# Bluetooth.net
KiCad netlist of a schematic drawn in Altium Designer
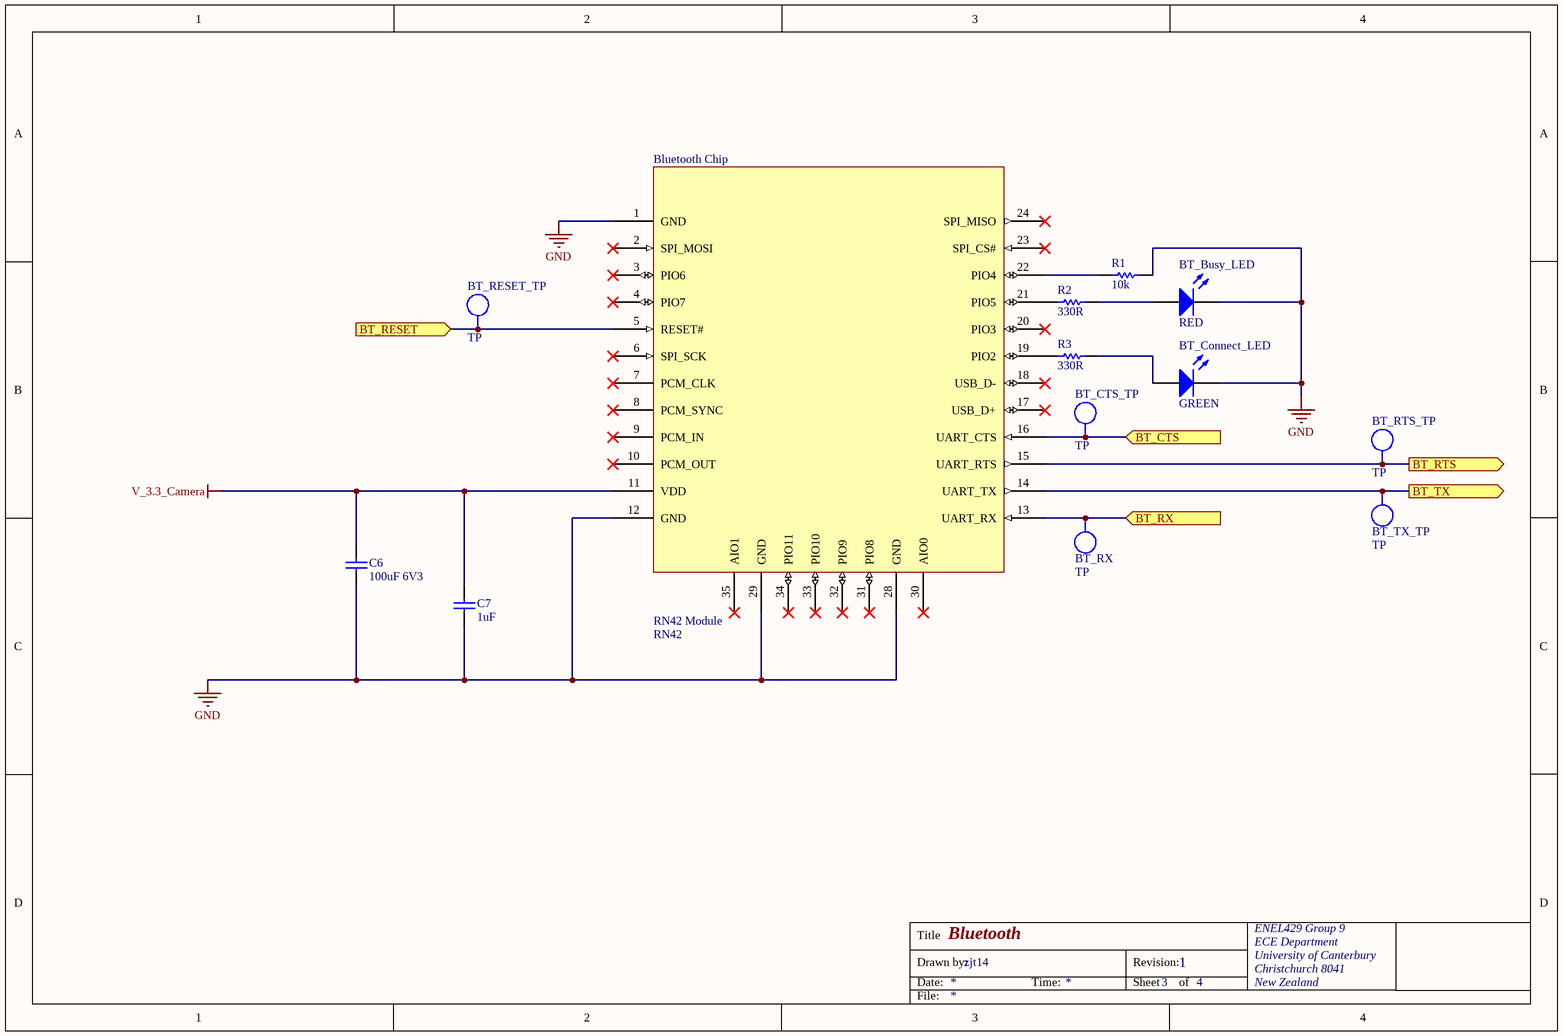
[diagram p0: Bluetooth.SchDoc]

(export (version "E")
  (design (tool "Eeschema 10.0.6"))
  (components
    (comp (ref "Bluetooth Chip")
      (value "RN42 Module")
      (footprint "RN42-LAND")
      (fields (field (name "ALTIUM_VALUE") "RN42") (field (name "MANUFACTURER") "Roving Networks"))
      (libsource (lib "Dwl-Altium-Schematic-Symbol-Library") (part "RN42MOD"))
    )
    (comp (ref "BT_Busy_LED")
      (value "RED")
      (footprint "Diode_0805")
      (description "Red LED 0805")
      (fields (field (name "PART NUMBER") "DL_LED Red 0805") (field (name "MANUFACTURER") "Vishay"))
      (libsource (lib "ENEL429_4") (part "DL_LED Red 0805"))
    )
    (comp (ref "BT_Connect_LED")
      (value "GREEN")
      (footprint "DIODE_0805")
      (description "Green LED 0805")
      (fields (field (name "PART NUMBER") "DL_LED Green 0805") (field (name "MANUFACTURER") "Vishay"))
      (libsource (lib "ENEL429_4") (part "DL_LED Green 0805"))
    )
    (comp (ref "BT_CTS_TP")
      (value "TP")
      (footprint "TEST_POINT_4X2MM")
      (description "Test-Point")
      (fields (field (name "PART NUMBER") "TP_TESTPOINT"))
      (libsource (lib "ENEL429_4") (part "TP_TESTPOINT"))
    )
    (comp (ref "BT_RESET_TP")
      (value "TP")
      (footprint "TEST_POINT_4X2MM")
      (description "Test-Point")
      (fields (field (name "PART NUMBER") "TP_TESTPOINT"))
      (libsource (lib "ENEL429_4") (part "TP_TESTPOINT"))
    )
    (comp (ref "BT_RTS_TP")
      (value "TP")
      (footprint "TEST_POINT_4X2MM")
      (description "Test-Point")
      (fields (field (name "PART NUMBER") "TP_TESTPOINT"))
      (libsource (lib "ENEL429_4") (part "TP_TESTPOINT"))
    )
    (comp (ref "BT_RX")
      (value "TP")
      (footprint "TEST_POINT_4X2MM")
      (description "Test-Point")
      (fields (field (name "PART NUMBER") "TP_TESTPOINT"))
      (libsource (lib "ENEL429_4") (part "TP_TESTPOINT"))
    )
    (comp (ref "BT_TX_TP")
      (value "TP")
      (footprint "TEST_POINT_4X2MM")
      (description "Test-Point")
      (fields (field (name "PART NUMBER") "TP_TESTPOINT"))
      (libsource (lib "ENEL429_4") (part "TP_TESTPOINT"))
    )
    (comp (ref "C6")
      (value "100uF 6V3")
      (footprint "1206")
      (description "100uF 6.3V 1206 multi-layer ceramic capacitor")
      (fields (field (name "PART NUMBER") "CP_CER 100uF_1206_6V3") (field (name "MANUFACTURER") "Kemet"))
      (libsource (lib "ENEL429_4") (part "CP_CER 100uF_1206_6V3"))
    )
    (comp (ref "C7")
      (value "1uF")
      (footprint "0603")
      (description "CAP CER 1.0UF 50V X7R 0603")
      (fields (field (name "PART NUMBER") "CP_1uF_50V_0603") (field (name "MANUFACTURER") "Taiyo Yuden"))
      (libsource (lib "ENEL429_4") (part "CP_1uF_50V_0603"))
    )
    (comp (ref "R1")
      (value "10k")
      (footprint "0603")
      (description "RES 10.0K OHM 1/10W 1% 0603 SMD")
      (fields (field (name "PART NUMBER") "RS_10k 0603") (field (name "MANUFACTURER") "Yageo"))
      (libsource (lib "ENEL429_4") (part "RS_10k 0603"))
    )
    (comp (ref "R2")
      (value "330R")
      (footprint "0603")
      (description "RES 330 OHM 1/10W 1% 0603 SMD")
      (fields (field (name "PART NUMBER") "RS_330R 0603") (field (name "MANUFACTURER") "Yageo"))
      (libsource (lib "ENEL429_4") (part "RS_330R 0603"))
    )
    (comp (ref "R3")
      (value "330R")
      (footprint "0603")
      (description "RES 330 OHM 1/10W 1% 0603 SMD")
      (fields (field (name "PART NUMBER") "RS_330R 0603") (field (name "MANUFACTURER") "Yageo"))
      (libsource (lib "ENEL429_4") (part "RS_330R 0603"))
    )
  )
  (nets
    (net (code "1") (name "/BT_CTS") (class "Default")
      (node (ref "BT_CTS_TP") (pin "1") (pinfunction "1_1") (pintype "passive"))
      (node (ref "Bluetooth Chip") (pin "16") (pinfunction "UART_CTS_16") (pintype "input"))
    )
    (net (code "2") (name "/BT_RESET") (class "Default")
      (node (ref "BT_RESET_TP") (pin "1") (pinfunction "1_1") (pintype "passive"))
      (node (ref "Bluetooth Chip") (pin "5") (pinfunction "RESET#_5") (pintype "input"))
    )
    (net (code "3") (name "/BT_RTS") (class "Default")
      (node (ref "BT_RTS_TP") (pin "1") (pinfunction "1_1") (pintype "passive"))
      (node (ref "Bluetooth Chip") (pin "15") (pinfunction "UART_RTS_15") (pintype "output"))
    )
    (net (code "4") (name "/BT_RX") (class "Default")
      (node (ref "BT_RX") (pin "1") (pinfunction "1_1") (pintype "passive"))
      (node (ref "Bluetooth Chip") (pin "13") (pinfunction "UART_RX_13") (pintype "input"))
    )
    (net (code "5") (name "/BT_TX") (class "Default")
      (node (ref "BT_TX_TP") (pin "1") (pinfunction "1_1") (pintype "passive"))
      (node (ref "Bluetooth Chip") (pin "14") (pinfunction "UART_TX_14") (pintype "output"))
    )
    (net (code "6") (name "GND") (class "Default")
      (node (ref "BT_Busy_LED") (pin "2") (pinfunction "K_2") (pintype "passive"))
      (node (ref "BT_Connect_LED") (pin "2") (pinfunction "K_2") (pintype "passive"))
      (node (ref "Bluetooth Chip") (pin "1") (pinfunction "GND_1") (pintype "power_in"))
      (node (ref "Bluetooth Chip") (pin "12") (pinfunction "GND_12") (pintype "power_in"))
      (node (ref "Bluetooth Chip") (pin "28") (pinfunction "GND_28") (pintype "power_in"))
      (node (ref "Bluetooth Chip") (pin "29") (pinfunction "GND_29") (pintype "power_in"))
      (node (ref "C6") (pin "2") (pinfunction "2_2") (pintype "passive"))
      (node (ref "C7") (pin "2") (pinfunction "2_2") (pintype "passive"))
      (node (ref "R1") (pin "2") (pinfunction "2_2") (pintype "passive"))
    )
    (net (code "7") (name "Net-(BT_Busy_LED-A)") (class "Default")
      (node (ref "BT_Busy_LED") (pin "1") (pinfunction "A_1") (pintype "passive"))
      (node (ref "R2") (pin "2") (pinfunction "2_2") (pintype "passive"))
    )
    (net (code "8") (name "Net-(BT_Connect_LED-A)") (class "Default")
      (node (ref "BT_Connect_LED") (pin "1") (pinfunction "A_1") (pintype "passive"))
      (node (ref "R3") (pin "2") (pinfunction "2_2") (pintype "passive"))
    )
    (net (code "9") (name "Net-(Bluetooth Chip-PIO2)") (class "Default")
      (node (ref "Bluetooth Chip") (pin "19") (pinfunction "PIO2_19") (pintype "bidirectional"))
      (node (ref "R3") (pin "1") (pinfunction "1_1") (pintype "passive"))
    )
    (net (code "10") (name "Net-(Bluetooth Chip-PIO4)") (class "Default")
      (node (ref "Bluetooth Chip") (pin "22") (pinfunction "PIO4_22") (pintype "bidirectional"))
      (node (ref "R1") (pin "1") (pinfunction "1_1") (pintype "passive"))
    )
    (net (code "11") (name "Net-(Bluetooth Chip-PIO5)") (class "Default")
      (node (ref "Bluetooth Chip") (pin "21") (pinfunction "PIO5_21") (pintype "bidirectional"))
      (node (ref "R2") (pin "1") (pinfunction "1_1") (pintype "passive"))
    )
    (net (code "12") (name "V_3.3_Camera") (class "Default")
      (node (ref "Bluetooth Chip") (pin "11") (pinfunction "VDD_11") (pintype "power_in"))
      (node (ref "C6") (pin "1") (pinfunction "1_1") (pintype "passive"))
      (node (ref "C7") (pin "1") (pinfunction "1_1") (pintype "passive"))
    )
    (net (code "13") (name "unconnected-(Bluetooth Chip-AIO0-Pad30)") (class "Default")
      (node (ref "Bluetooth Chip") (pin "30") (pinfunction "AIO0_30") (pintype "passive+no_connect"))
    )
    (net (code "14") (name "unconnected-(Bluetooth Chip-AIO1-Pad35)") (class "Default")
      (node (ref "Bluetooth Chip") (pin "35") (pinfunction "AIO1_35") (pintype "passive+no_connect"))
    )
    (net (code "15") (name "unconnected-(Bluetooth Chip-PCM_CLK-Pad7)") (class "Default")
      (node (ref "Bluetooth Chip") (pin "7") (pinfunction "PCM_CLK_7") (pintype "passive+no_connect"))
    )
    (net (code "16") (name "unconnected-(Bluetooth Chip-PCM_IN-Pad9)") (class "Default")
      (node (ref "Bluetooth Chip") (pin "9") (pinfunction "PCM_IN_9") (pintype "passive+no_connect"))
    )
    (net (code "17") (name "unconnected-(Bluetooth Chip-PCM_OUT-Pad10)") (class "Default")
      (node (ref "Bluetooth Chip") (pin "10") (pinfunction "PCM_OUT_10") (pintype "passive+no_connect"))
    )
    (net (code "18") (name "unconnected-(Bluetooth Chip-PCM_SYNC-Pad8)") (class "Default")
      (node (ref "Bluetooth Chip") (pin "8") (pinfunction "PCM_SYNC_8") (pintype "passive+no_connect"))
    )
    (net (code "19") (name "unconnected-(Bluetooth Chip-PIO3-Pad20)") (class "Default")
      (node (ref "Bluetooth Chip") (pin "20") (pinfunction "PIO3_20") (pintype "bidirectional+no_connect"))
    )
    (net (code "20") (name "unconnected-(Bluetooth Chip-PIO6-Pad3)") (class "Default")
      (node (ref "Bluetooth Chip") (pin "3") (pinfunction "PIO6_3") (pintype "bidirectional+no_connect"))
    )
    (net (code "21") (name "unconnected-(Bluetooth Chip-PIO7-Pad4)") (class "Default")
      (node (ref "Bluetooth Chip") (pin "4") (pinfunction "PIO7_4") (pintype "bidirectional+no_connect"))
    )
    (net (code "22") (name "unconnected-(Bluetooth Chip-PIO8-Pad31)") (class "Default")
      (node (ref "Bluetooth Chip") (pin "31") (pinfunction "PIO8_31") (pintype "bidirectional+no_connect"))
    )
    (net (code "23") (name "unconnected-(Bluetooth Chip-PIO9-Pad32)") (class "Default")
      (node (ref "Bluetooth Chip") (pin "32") (pinfunction "PIO9_32") (pintype "bidirectional+no_connect"))
    )
    (net (code "24") (name "unconnected-(Bluetooth Chip-PIO10-Pad33)") (class "Default")
      (node (ref "Bluetooth Chip") (pin "33") (pinfunction "PIO10_33") (pintype "bidirectional+no_connect"))
    )
    (net (code "25") (name "unconnected-(Bluetooth Chip-PIO11-Pad34)") (class "Default")
      (node (ref "Bluetooth Chip") (pin "34") (pinfunction "PIO11_34") (pintype "bidirectional+no_connect"))
    )
    (net (code "26") (name "unconnected-(Bluetooth Chip-SPI_CS#-Pad23)") (class "Default")
      (node (ref "Bluetooth Chip") (pin "23") (pinfunction "SPI_CS#_23") (pintype "input+no_connect"))
    )
    (net (code "27") (name "unconnected-(Bluetooth Chip-SPI_MISO-Pad24)") (class "Default")
      (node (ref "Bluetooth Chip") (pin "24") (pinfunction "SPI_MISO_24") (pintype "output+no_connect"))
    )
    (net (code "28") (name "unconnected-(Bluetooth Chip-SPI_MOSI-Pad2)") (class "Default")
      (node (ref "Bluetooth Chip") (pin "2") (pinfunction "SPI_MOSI_2") (pintype "input+no_connect"))
    )
    (net (code "29") (name "unconnected-(Bluetooth Chip-SPI_SCK-Pad6)") (class "Default")
      (node (ref "Bluetooth Chip") (pin "6") (pinfunction "SPI_SCK_6") (pintype "input+no_connect"))
    )
    (net (code "30") (name "unconnected-(Bluetooth Chip-USB_D+-Pad17)") (class "Default")
      (node (ref "Bluetooth Chip") (pin "17") (pinfunction "USB_D+_17") (pintype "bidirectional+no_connect"))
    )
    (net (code "31") (name "unconnected-(Bluetooth Chip-USB_D--Pad18)") (class "Default")
      (node (ref "Bluetooth Chip") (pin "18") (pinfunction "USB_D-_18") (pintype "bidirectional+no_connect"))
    )
  )
)
